# ftdi.net
KiCad netlist of a schematic drawn in EAGLE
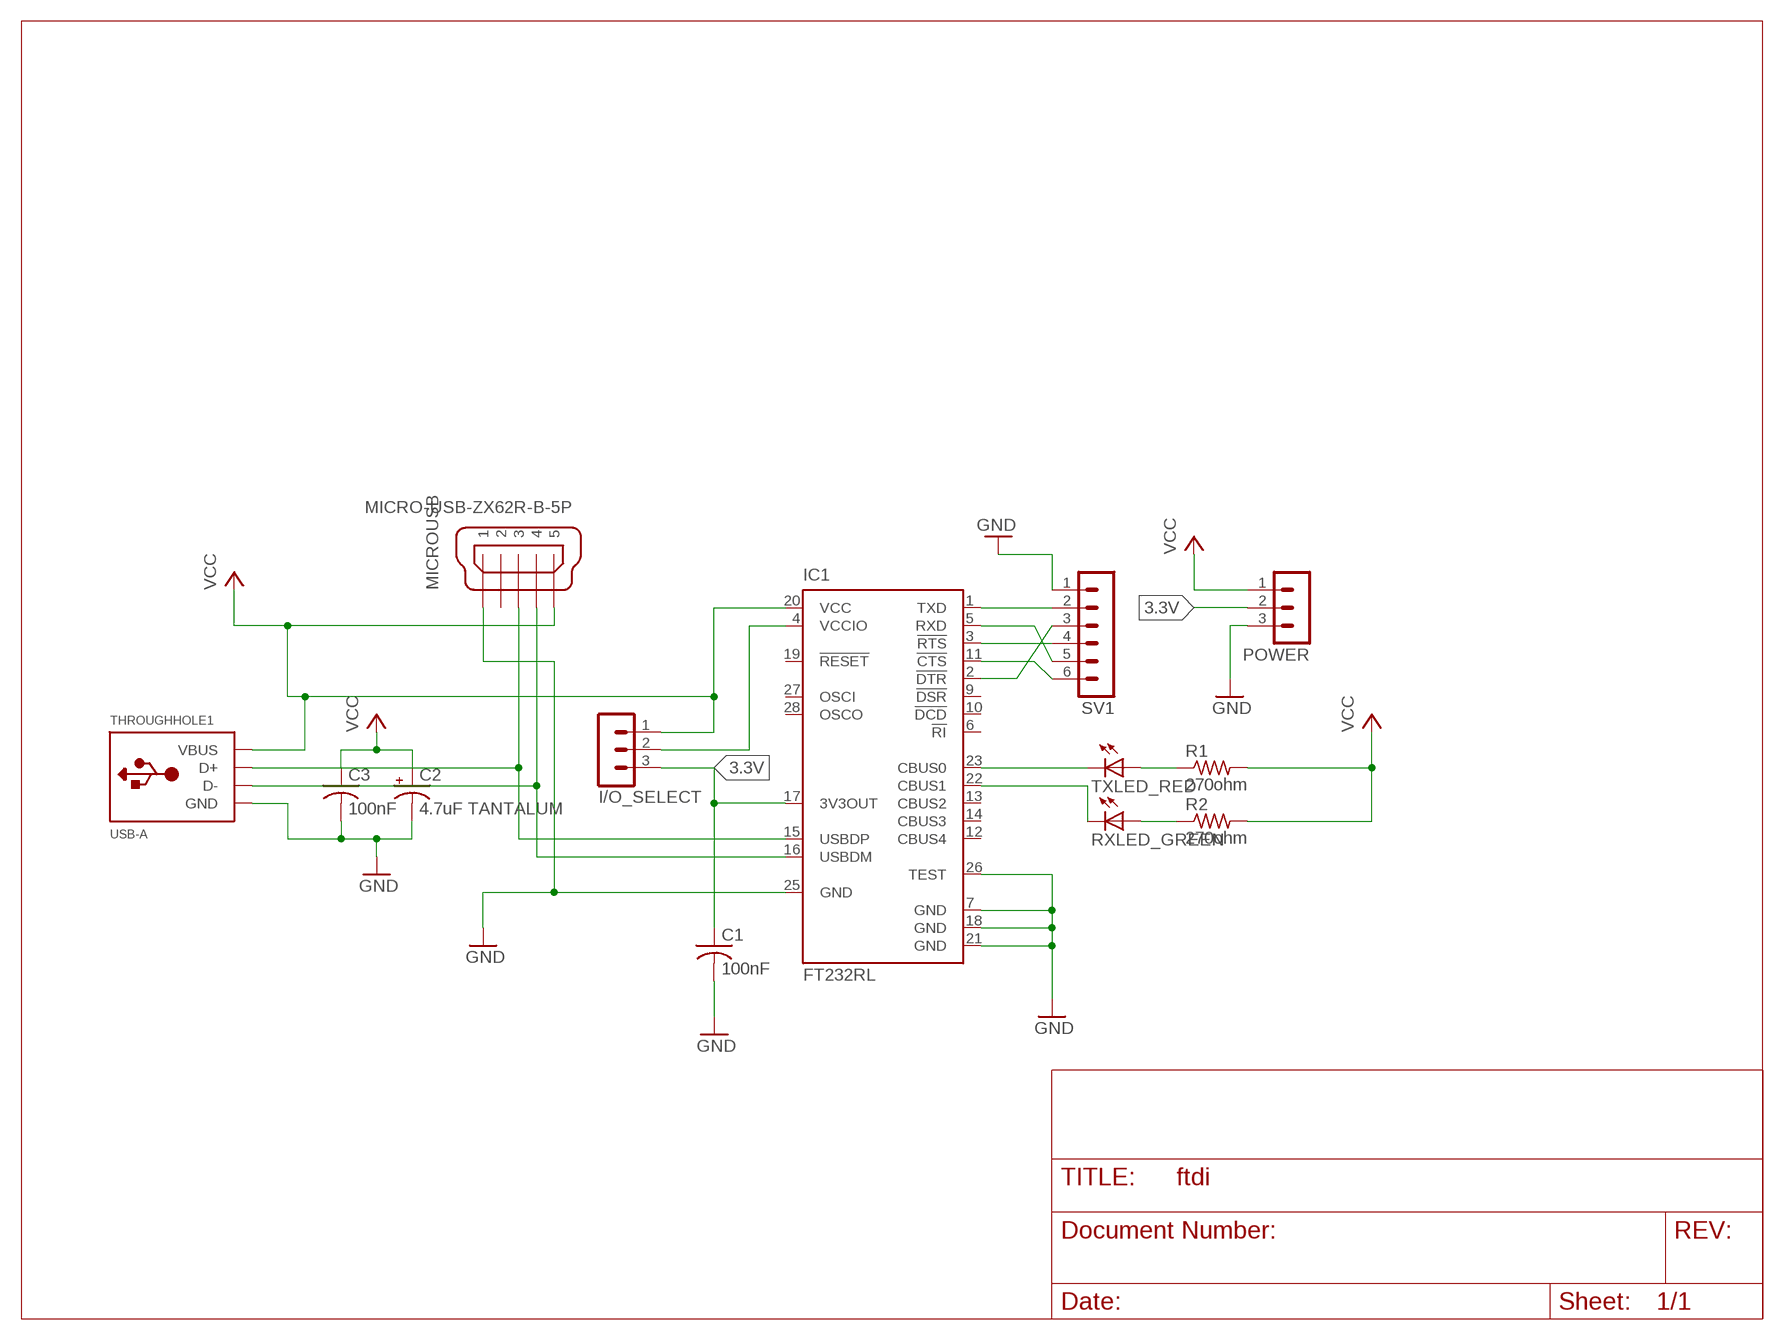
[diagram p0: schematic, sheet 1]

(export (version "E")
  (design (tool "Eeschema 10.0.6"))
  (components
    (comp (ref "C1")
      (value "100nF")
      (footprint "eagle-import:C1206")
      (libsource (lib "eagle-import") (part "C-USC1206"))
    )
    (comp (ref "C2")
      (value "4.7uF TANTALUM")
      (footprint "eagle-import:C_6032-28R")
      (libsource (lib "eagle-import") (part "CPOL-USC/6032-28R"))
    )
    (comp (ref "C3")
      (value "100nF")
      (footprint "eagle-import:C1206")
      (libsource (lib "eagle-import") (part "C-USC1206"))
    )
    (comp (ref "I/O_SELECT")
      (value "MA03-1")
      (footprint "eagle-import:MA03-1")
      (libsource (lib "eagle-import") (part "MA03-1"))
    )
    (comp (ref "IC1")
      (value "FT232RL")
      (footprint "eagle-import:SSOP28")
      (libsource (lib "eagle-import") (part "FT232RL"))
    )
    (comp (ref "MICROUSB")
      (value "MICRO-USB-ZX62R-B-5P")
      (footprint "eagle-import:ZX62R-B-5P")
      (libsource (lib "eagle-import") (part "MICRO-USB-ZX62R-B-5P"))
    )
    (comp (ref "POWER")
      (value "MA03-1")
      (footprint "eagle-import:MA03-1")
      (libsource (lib "eagle-import") (part "MA03-1"))
    )
    (comp (ref "R1")
      (value "270ohm")
      (footprint "eagle-import:R1206")
      (libsource (lib "eagle-import") (part "R-US_R1206"))
    )
    (comp (ref "R2")
      (value "270ohm")
      (footprint "eagle-import:R1206")
      (libsource (lib "eagle-import") (part "R-US_R1206"))
    )
    (comp (ref "RXLED_GREEN")
      (value "LED3MM")
      (footprint "eagle-import:LED3MM")
      (libsource (lib "eagle-import") (part "LED3MM"))
    )
    (comp (ref "SV1")
      (value "MA06-1")
      (footprint "eagle-import:MA06-1")
      (libsource (lib "eagle-import") (part "MA06-1"))
    )
    (comp (ref "THROUGHHOLE1")
      (value "USB-A")
      (footprint "eagle-import:MOLEX_480371000")
      (libsource (lib "eagle-import") (part "USB-A"))
    )
    (comp (ref "TXLED_RED")
      (value "LED3MM")
      (footprint "eagle-import:LED3MM")
      (libsource (lib "eagle-import") (part "LED3MM"))
    )
  )
  (nets
    (net (code "1") (name "3.3V") (class "Default")
      (node (ref "C1") (pin "1") (pinfunction "1_1") (pintype "passive"))
      (node (ref "I/O_SELECT") (pin "3") (pinfunction "3_3") (pintype "passive"))
      (node (ref "IC1") (pin "17") (pinfunction "3V3OUT_17") (pintype "output"))
      (node (ref "POWER") (pin "2") (pinfunction "2_2") (pintype "passive"))
    )
    (net (code "2") (name "GND") (class "Default")
      (node (ref "C1") (pin "2") (pinfunction "2_2") (pintype "passive"))
      (node (ref "C2") (pin "-") (pinfunction "-_-") (pintype "passive"))
      (node (ref "C3") (pin "2") (pinfunction "2_2") (pintype "passive"))
      (node (ref "IC1") (pin "18") (pinfunction "GND_18") (pintype "power_in"))
      (node (ref "IC1") (pin "21") (pinfunction "GND_21") (pintype "power_in"))
      (node (ref "IC1") (pin "25") (pinfunction "GND_25") (pintype "power_in"))
      (node (ref "IC1") (pin "26") (pinfunction "TEST_26") (pintype "input"))
      (node (ref "IC1") (pin "7") (pinfunction "GND_7") (pintype "power_in"))
      (node (ref "MICROUSB") (pin "1") (pinfunction "1_1") (pintype "input"))
      (node (ref "POWER") (pin "3") (pinfunction "3_3") (pintype "passive"))
      (node (ref "SV1") (pin "1") (pinfunction "1_1") (pintype "passive"))
      (node (ref "THROUGHHOLE1") (pin "P$4") (pinfunction "GND_P$4") (pintype "power_in"))
    )
    (net (code "3") (name "Net-(IC1-CBUS0)") (class "Default")
      (node (ref "IC1") (pin "23") (pinfunction "CBUS0_23") (pintype "bidirectional"))
      (node (ref "TXLED_RED") (pin "K") (pinfunction "C_K") (pintype "passive"))
    )
    (net (code "4") (name "Net-(IC1-CBUS1)") (class "Default")
      (node (ref "IC1") (pin "22") (pinfunction "CBUS1_22") (pintype "bidirectional"))
      (node (ref "RXLED_GREEN") (pin "K") (pinfunction "C_K") (pintype "passive"))
    )
    (net (code "5") (name "Net-(IC1-RXD)") (class "Default")
      (node (ref "IC1") (pin "5") (pinfunction "RXD_5") (pintype "input"))
      (node (ref "SV1") (pin "5") (pinfunction "5_5") (pintype "passive"))
    )
    (net (code "6") (name "Net-(IC1-TXD)") (class "Default")
      (node (ref "IC1") (pin "1") (pinfunction "TXD_1") (pintype "output"))
      (node (ref "SV1") (pin "2") (pinfunction "2_2") (pintype "passive"))
    )
    (net (code "7") (name "Net-(IC1-USBDM)") (class "Default")
      (node (ref "IC1") (pin "16") (pinfunction "USBDM_16") (pintype "bidirectional"))
      (node (ref "MICROUSB") (pin "4") (pinfunction "4_4") (pintype "input"))
      (node (ref "THROUGHHOLE1") (pin "P$2") (pinfunction "D-_P$2") (pintype "bidirectional"))
    )
    (net (code "8") (name "Net-(IC1-USBDP)") (class "Default")
      (node (ref "IC1") (pin "15") (pinfunction "USBDP_15") (pintype "bidirectional"))
      (node (ref "MICROUSB") (pin "3") (pinfunction "3_3") (pintype "input"))
      (node (ref "THROUGHHOLE1") (pin "P$3") (pinfunction "D+_P$3") (pintype "bidirectional"))
    )
    (net (code "9") (name "Net-(IC1-VCCIO)") (class "Default")
      (node (ref "I/O_SELECT") (pin "2") (pinfunction "2_2") (pintype "passive"))
      (node (ref "IC1") (pin "4") (pinfunction "VCCIO_4") (pintype "power_in"))
    )
    (net (code "10") (name "Net-(IC1-~{CTS})") (class "Default")
      (node (ref "IC1") (pin "11") (pinfunction "~{CTS}_11") (pintype "input"))
      (node (ref "SV1") (pin "6") (pinfunction "6_6") (pintype "passive"))
    )
    (net (code "11") (name "Net-(IC1-~{DTR})") (class "Default")
      (node (ref "IC1") (pin "2") (pinfunction "~{DTR}_2") (pintype "output"))
      (node (ref "SV1") (pin "3") (pinfunction "3_3") (pintype "passive"))
    )
    (net (code "12") (name "Net-(IC1-~{RTS})") (class "Default")
      (node (ref "IC1") (pin "3") (pinfunction "~{RTS}_3") (pintype "output"))
      (node (ref "SV1") (pin "4") (pinfunction "4_4") (pintype "passive"))
    )
    (net (code "13") (name "Net-(R1-Pad1)") (class "Default")
      (node (ref "R1") (pin "1") (pinfunction "1_1") (pintype "passive"))
      (node (ref "TXLED_RED") (pin "A") (pinfunction "A_A") (pintype "passive"))
    )
    (net (code "14") (name "Net-(R2-Pad1)") (class "Default")
      (node (ref "R2") (pin "1") (pinfunction "1_1") (pintype "passive"))
      (node (ref "RXLED_GREEN") (pin "A") (pinfunction "A_A") (pintype "passive"))
    )
    (net (code "15") (name "VCC") (class "Default")
      (node (ref "C2") (pin "+") (pinfunction "+_+") (pintype "passive"))
      (node (ref "C3") (pin "1") (pinfunction "1_1") (pintype "passive"))
      (node (ref "I/O_SELECT") (pin "1") (pinfunction "1_1") (pintype "passive"))
      (node (ref "IC1") (pin "20") (pinfunction "VCC_20") (pintype "power_in"))
      (node (ref "MICROUSB") (pin "5") (pinfunction "5_5") (pintype "input"))
      (node (ref "POWER") (pin "1") (pinfunction "1_1") (pintype "passive"))
      (node (ref "R1") (pin "2") (pinfunction "2_2") (pintype "passive"))
      (node (ref "R2") (pin "2") (pinfunction "2_2") (pintype "passive"))
      (node (ref "THROUGHHOLE1") (pin "P$1") (pinfunction "VBUS_P$1") (pintype "power_in"))
    )
    (net (code "16") (name "unconnected-(IC1-CBUS2-Pad13)") (class "Default")
      (node (ref "IC1") (pin "13") (pinfunction "CBUS2_13") (pintype "bidirectional"))
    )
    (net (code "17") (name "unconnected-(IC1-CBUS3-Pad14)") (class "Default")
      (node (ref "IC1") (pin "14") (pinfunction "CBUS3_14") (pintype "bidirectional"))
    )
    (net (code "18") (name "unconnected-(IC1-CBUS4-Pad12)") (class "Default")
      (node (ref "IC1") (pin "12") (pinfunction "CBUS4_12") (pintype "bidirectional"))
    )
    (net (code "19") (name "unconnected-(IC1-OSCI-Pad27)") (class "Default")
      (node (ref "IC1") (pin "27") (pinfunction "OSCI_27") (pintype "input"))
    )
    (net (code "20") (name "unconnected-(IC1-OSCO-Pad28)") (class "Default")
      (node (ref "IC1") (pin "28") (pinfunction "OSCO_28") (pintype "output"))
    )
    (net (code "21") (name "unconnected-(IC1-~{DCD}-Pad10)") (class "Default")
      (node (ref "IC1") (pin "10") (pinfunction "~{DCD}_10") (pintype "input"))
    )
    (net (code "22") (name "unconnected-(IC1-~{DSR}-Pad9)") (class "Default")
      (node (ref "IC1") (pin "9") (pinfunction "~{DSR}_9") (pintype "input"))
    )
    (net (code "23") (name "unconnected-(IC1-~{RESET}-Pad19)") (class "Default")
      (node (ref "IC1") (pin "19") (pinfunction "~{RESET}_19") (pintype "input"))
    )
    (net (code "24") (name "unconnected-(IC1-~{RI}-Pad6)") (class "Default")
      (node (ref "IC1") (pin "6") (pinfunction "~{RI}_6") (pintype "input"))
    )
    (net (code "25") (name "unconnected-(MICROUSB-Pad2)") (class "Default")
      (node (ref "MICROUSB") (pin "2") (pinfunction "2_2") (pintype "input"))
    )
  )
)
